# 09_-_Ethernet.net
KiCad netlist of a schematic drawn in Altium Designer
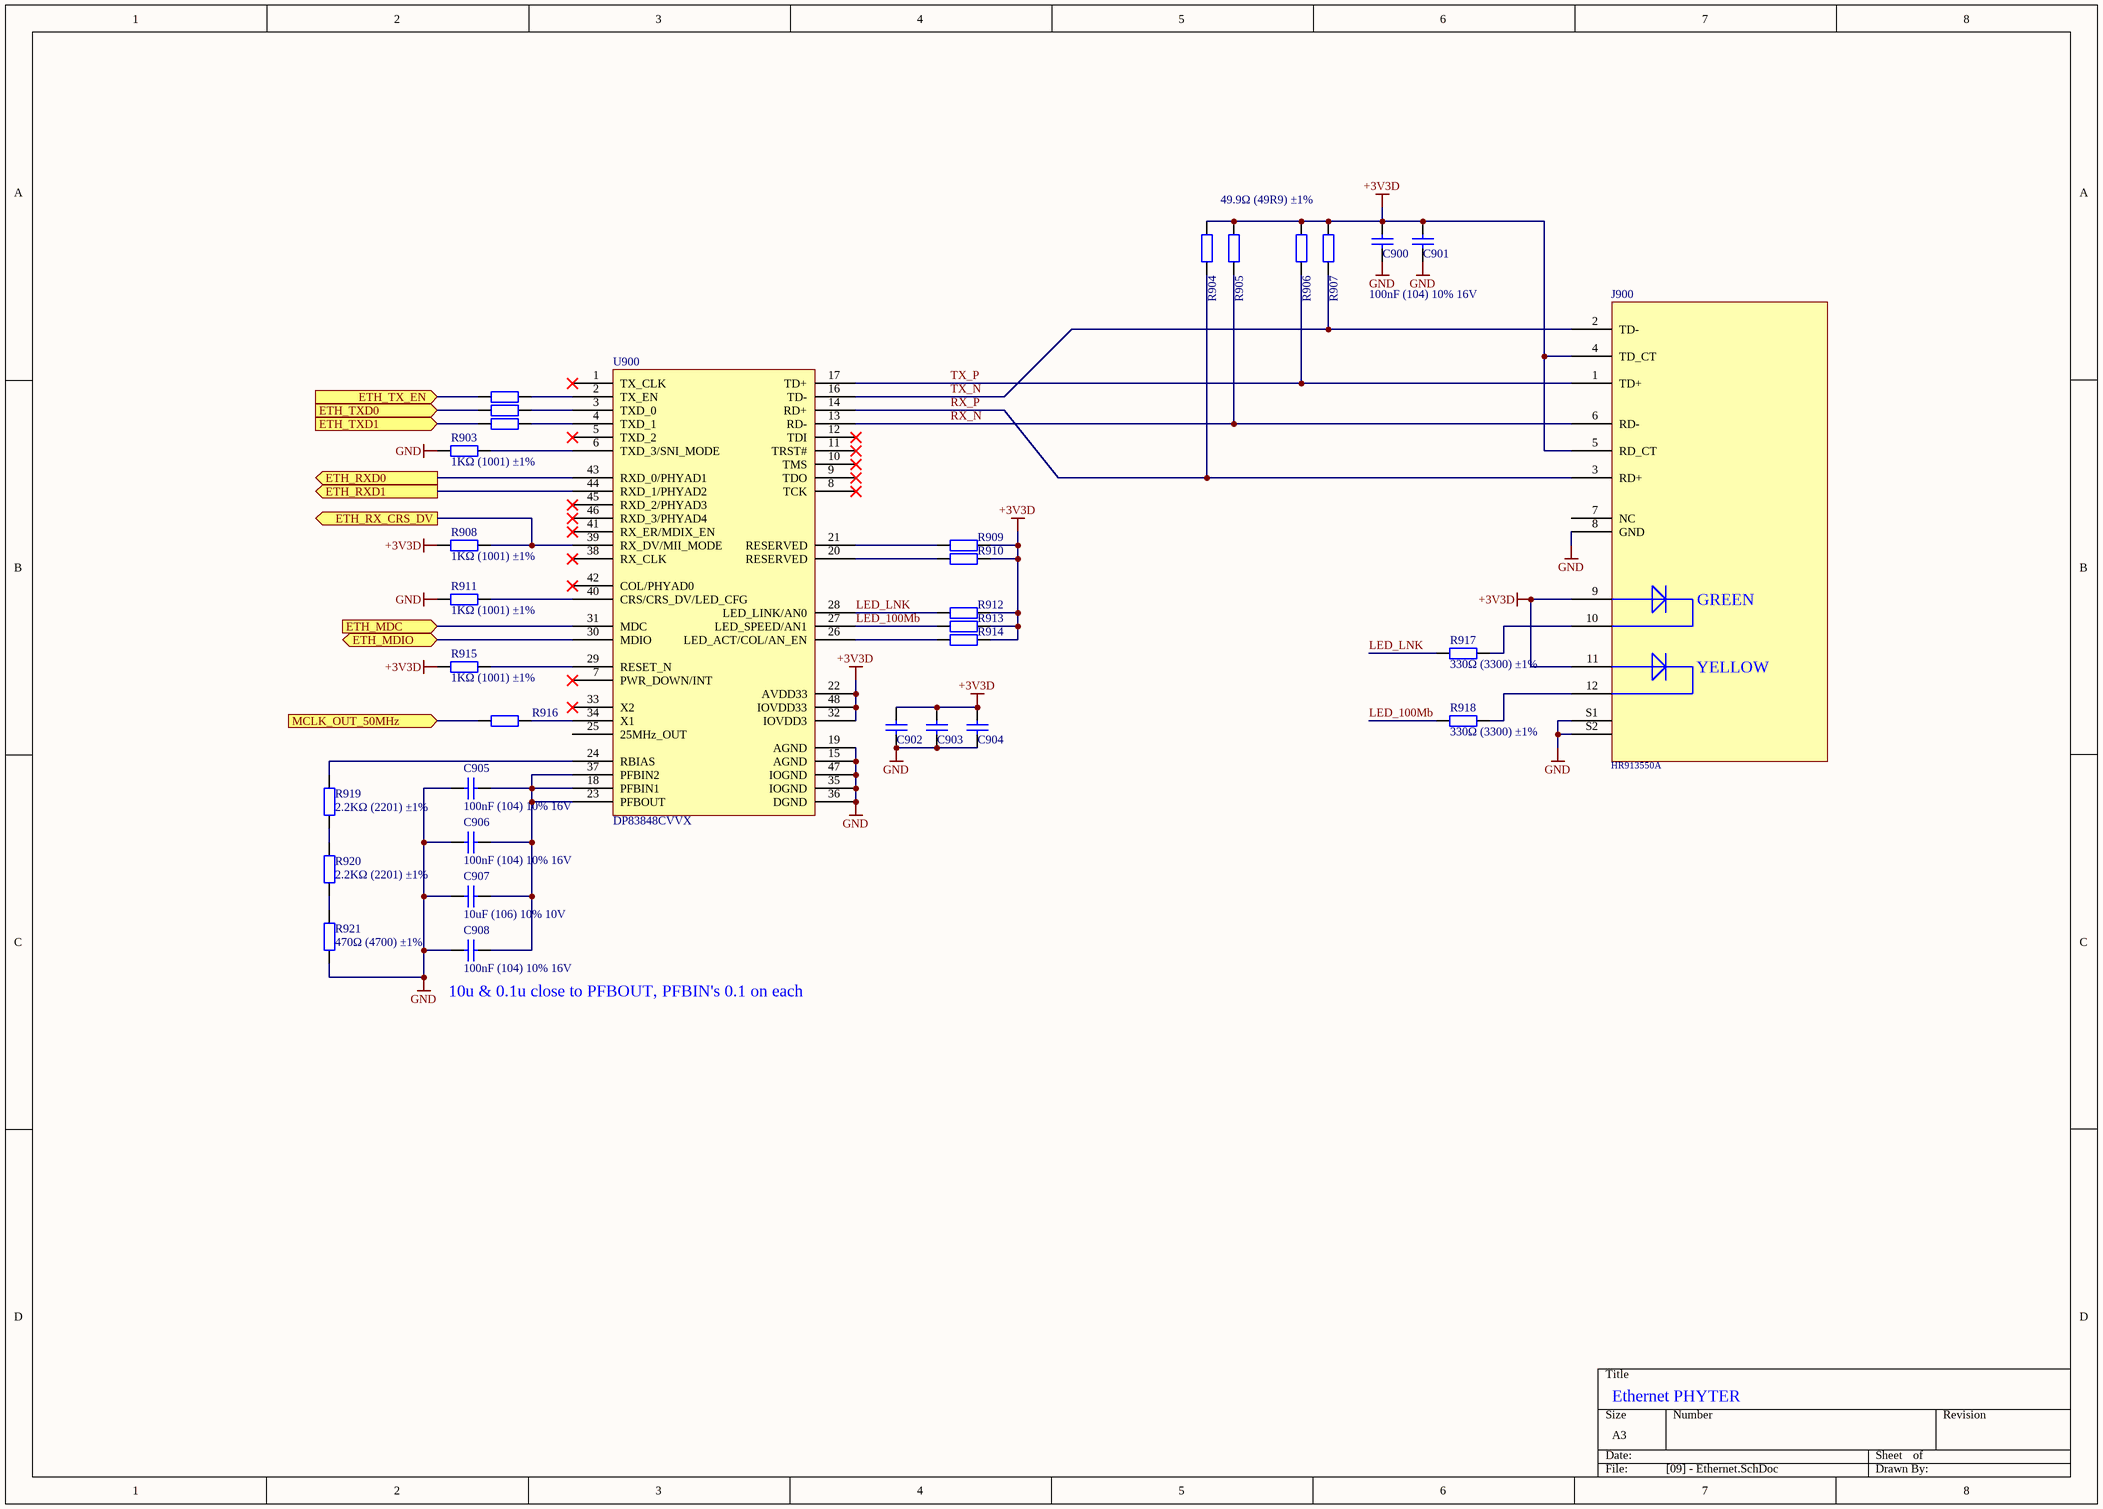
[diagram p0: [09] - Ethernet.SchDoc]

(export (version "E")
  (design (tool "Eeschema 10.0.6"))
  (components
    (comp (ref "C900")
      (value "100nF (104) 10% 16V")
      (footprint "0402_C")
      (description "贴片电容")
      (libsource (lib "Cap") (part "0402 100nF (104) 10% 16V"))
    )
    (comp (ref "C901")
      (value "100nF (104) 10% 16V")
      (footprint "0402_C")
      (description "贴片电容")
      (libsource (lib "Cap") (part "0402 100nF (104) 10% 16V"))
    )
    (comp (ref "C902")
      (value "100nF (104) 10% 16V")
      (footprint "0402_C")
      (description "贴片电容")
      (libsource (lib "Cap") (part "0402 100nF (104) 10% 16V"))
    )
    (comp (ref "C903")
      (value "100nF (104) 10% 16V")
      (footprint "0402_C")
      (description "贴片电容")
      (libsource (lib "Cap") (part "0402 100nF (104) 10% 16V"))
    )
    (comp (ref "C904")
      (value "100nF (104) 10% 16V")
      (footprint "0402_C")
      (description "贴片电容")
      (libsource (lib "Cap") (part "0402 100nF (104) 10% 16V"))
    )
    (comp (ref "C905")
      (value "100nF (104) 10% 16V")
      (footprint "0402_C")
      (description "贴片电容")
      (libsource (lib "Cap") (part "0402 100nF (104) 10% 16V"))
    )
    (comp (ref "C906")
      (value "100nF (104) 10% 16V")
      (footprint "0402_C")
      (description "贴片电容")
      (libsource (lib "Cap") (part "0402 100nF (104) 10% 16V"))
    )
    (comp (ref "C907")
      (value "10uF (106) 10% 10V")
      (footprint "0603_C")
      (description "贴片电容")
      (libsource (lib "Cap") (part "0603 10uF (106) 10% 10V"))
    )
    (comp (ref "C908")
      (value "100nF (104) 10% 16V")
      (footprint "0402_C")
      (description "贴片电容")
      (libsource (lib "Cap") (part "0402 100nF (104) 10% 16V"))
    )
    (comp (ref "J900")
      (value "HR913550A")
      (footprint "RJ45 MagJack")
      (description "RJ45 12 1 Green - Yellow Through Hole Ethernet Connectors/Modular Connectors (RJ45 RJ11) RoHS")
      (libsource (lib "FPGA_PMU_lib") (part "HR913550A"))
    )
    (comp (ref "R900")
      (value "49.9Ω (49R9) ±1%")
      (footprint "0402_R")
      (description "贴片电阻")
      (libsource (lib "RES") (part "0402 49.9Ω (49R9) 1%"))
    )
    (comp (ref "R901")
      (value "49.9Ω (49R9) ±1%")
      (footprint "0402_R")
      (description "贴片电阻")
      (libsource (lib "RES") (part "0402 49.9Ω (49R9) 1%"))
    )
    (comp (ref "R902")
      (value "49.9Ω (49R9) ±1%")
      (footprint "0402_R")
      (description "贴片电阻")
      (libsource (lib "RES") (part "0402 49.9Ω (49R9) 1%"))
    )
    (comp (ref "R903")
      (value "1KΩ (1001) ±1%")
      (footprint "0402_R")
      (description "贴片电阻")
      (libsource (lib "RES") (part "0402 1KΩ (1001) 1%"))
    )
    (comp (ref "R904")
      (value "49.9Ω (49R9) ±1%")
      (footprint "0402_R")
      (description "贴片电阻")
      (libsource (lib "") (part "0402 49.9Ω (49R9) 1%_1"))
    )
    (comp (ref "R905")
      (value "49.9Ω (49R9) ±1%")
      (footprint "0402_R")
      (description "贴片电阻")
      (libsource (lib "") (part "0402 49.9Ω (49R9) 1%_1"))
    )
    (comp (ref "R906")
      (value "49.9Ω (49R9) ±1%")
      (footprint "0402_R")
      (description "贴片电阻")
      (libsource (lib "") (part "0402 49.9Ω (49R9) 1%_1"))
    )
    (comp (ref "R907")
      (value "49.9Ω (49R9) ±1%")
      (footprint "0402_R")
      (description "贴片电阻")
      (libsource (lib "") (part "0402 49.9Ω (49R9) 1%_1"))
    )
    (comp (ref "R908")
      (value "1KΩ (1001) ±1%")
      (footprint "0402_R")
      (description "贴片电阻")
      (libsource (lib "RES") (part "0402 1KΩ (1001) 1%"))
    )
    (comp (ref "R909")
      (value "2.2KΩ (2201) ±1%")
      (footprint "0402_R")
      (description "贴片电阻")
      (libsource (lib "RES") (part "0402 2.2KΩ (2201) 1%"))
    )
    (comp (ref "R910")
      (value "2.2KΩ (2201) ±1%")
      (footprint "0402_R")
      (description "贴片电阻")
      (libsource (lib "RES") (part "0402 2.2KΩ (2201) 1%"))
    )
    (comp (ref "R911")
      (value "1KΩ (1001) ±1%")
      (footprint "0402_R")
      (description "贴片电阻")
      (libsource (lib "RES") (part "0402 1KΩ (1001) 1%"))
    )
    (comp (ref "R912")
      (value "2.2KΩ (2201) ±1%")
      (footprint "0402_R")
      (description "贴片电阻")
      (libsource (lib "RES") (part "0402 2.2KΩ (2201) 1%"))
    )
    (comp (ref "R913")
      (value "2.2KΩ (2201) ±1%")
      (footprint "0402_R")
      (description "贴片电阻")
      (libsource (lib "RES") (part "0402 2.2KΩ (2201) 1%"))
    )
    (comp (ref "R914")
      (value "2.2KΩ (2201) ±1%")
      (footprint "0402_R")
      (description "贴片电阻")
      (libsource (lib "RES") (part "0402 2.2KΩ (2201) 1%"))
    )
    (comp (ref "R915")
      (value "1KΩ (1001) ±1%")
      (footprint "0402_R")
      (description "贴片电阻")
      (libsource (lib "RES") (part "0402 1KΩ (1001) 1%"))
    )
    (comp (ref "R916")
      (value "49.9Ω (49R9) ±1%")
      (footprint "0402_R")
      (description "贴片电阻")
      (libsource (lib "RES") (part "0402 49.9Ω (49R9) 1%"))
    )
    (comp (ref "R917")
      (value "330Ω (3300) ±1%")
      (footprint "0603_R")
      (description "贴片电阻")
      (libsource (lib "RES") (part "0603 330Ω (3300) 1%"))
    )
    (comp (ref "R918")
      (value "330Ω (3300) ±1%")
      (footprint "0603_R")
      (description "贴片电阻")
      (libsource (lib "RES") (part "0603 330Ω (3300) 1%"))
    )
    (comp (ref "R919")
      (value "2.2KΩ (2201) ±1%")
      (footprint "0402_R")
      (description "贴片电阻")
      (libsource (lib "") (part "0402 2.2KΩ (2201) 1%_1"))
    )
    (comp (ref "R920")
      (value "2.2KΩ (2201) ±1%")
      (footprint "0402_R")
      (description "贴片电阻")
      (libsource (lib "") (part "0402 2.2KΩ (2201) 1%_1"))
    )
    (comp (ref "R921")
      (value "470Ω (4700) ±1%")
      (footprint "0402_R")
      (description "贴片电阻")
      (libsource (lib "RES") (part "0402 470Ω (4700) 1%"))
    )
    (comp (ref "U900")
      (value "DP83848CVVX")
      (footprint "LQFP-48_7x7x05P")
      (description "接口芯片")
      (libsource (lib "IC") (part "DP83848CVVX_[C16688]"))
    )
  )
  (nets
    (net (code "1") (name "+3V3D") (class "Default")
      (node (ref "C900") (pin "2") (pinfunction "2_2") (pintype "passive"))
      (node (ref "C901") (pin "2") (pinfunction "2_2") (pintype "passive"))
      (node (ref "C902") (pin "2") (pinfunction "2_2") (pintype "passive"))
      (node (ref "C903") (pin "2") (pinfunction "2_2") (pintype "passive"))
      (node (ref "C904") (pin "2") (pinfunction "2_2") (pintype "passive"))
      (node (ref "J900") (pin "11") (pinfunction "11_11") (pintype "passive"))
      (node (ref "J900") (pin "4") (pinfunction "TD_CT_4") (pintype "passive"))
      (node (ref "J900") (pin "5") (pinfunction "RD_CT_5") (pintype "passive"))
      (node (ref "J900") (pin "9") (pinfunction "9_9") (pintype "passive"))
      (node (ref "R904") (pin "2") (pinfunction "2_2") (pintype "passive"))
      (node (ref "R905") (pin "2") (pinfunction "2_2") (pintype "passive"))
      (node (ref "R906") (pin "2") (pinfunction "2_2") (pintype "passive"))
      (node (ref "R907") (pin "2") (pinfunction "2_2") (pintype "passive"))
      (node (ref "R908") (pin "1") (pinfunction "1_1") (pintype "passive"))
      (node (ref "R909") (pin "2") (pinfunction "2_2") (pintype "passive"))
      (node (ref "R910") (pin "2") (pinfunction "2_2") (pintype "passive"))
      (node (ref "R912") (pin "2") (pinfunction "2_2") (pintype "passive"))
      (node (ref "R913") (pin "2") (pinfunction "2_2") (pintype "passive"))
      (node (ref "R914") (pin "2") (pinfunction "2_2") (pintype "passive"))
      (node (ref "R915") (pin "1") (pinfunction "1_1") (pintype "passive"))
      (node (ref "U900") (pin "22") (pinfunction "AVDD33_22") (pintype "passive"))
      (node (ref "U900") (pin "32") (pinfunction "IOVDD3_32") (pintype "passive"))
      (node (ref "U900") (pin "48") (pinfunction "IOVDD33_48") (pintype "passive"))
    )
    (net (code "2") (name "/ETH_MDC") (class "Default")
      (node (ref "U900") (pin "31") (pinfunction "MDC_31") (pintype "passive"))
    )
    (net (code "3") (name "/ETH_MDIO") (class "Default")
      (node (ref "U900") (pin "30") (pinfunction "MDIO_30") (pintype "passive"))
    )
    (net (code "4") (name "/ETH_RXD0") (class "Default")
      (node (ref "U900") (pin "43") (pinfunction "RXD_0/PHYAD1_43") (pintype "passive"))
    )
    (net (code "5") (name "/ETH_RXD1") (class "Default")
      (node (ref "U900") (pin "44") (pinfunction "RXD_1/PHYAD2_44") (pintype "passive"))
    )
    (net (code "6") (name "/ETH_RX_CRS_DV") (class "Default")
      (node (ref "R908") (pin "2") (pinfunction "2_2") (pintype "passive"))
      (node (ref "U900") (pin "39") (pinfunction "RX_DV/MII_MODE_39") (pintype "passive"))
    )
    (net (code "7") (name "/ETH_TXD0") (class "Default")
      (node (ref "R901") (pin "1") (pinfunction "1_1") (pintype "passive"))
    )
    (net (code "8") (name "/ETH_TXD1") (class "Default")
      (node (ref "R902") (pin "1") (pinfunction "1_1") (pintype "passive"))
    )
    (net (code "9") (name "/ETH_TX_EN") (class "Default")
      (node (ref "R900") (pin "1") (pinfunction "1_1") (pintype "passive"))
    )
    (net (code "10") (name "/LED_100Mb") (class "Default")
      (node (ref "R913") (pin "1") (pinfunction "1_1") (pintype "passive"))
      (node (ref "R918") (pin "1") (pinfunction "1_1") (pintype "passive"))
      (node (ref "U900") (pin "27") (pinfunction "LED_SPEED/AN1_27") (pintype "passive"))
    )
    (net (code "11") (name "/LED_LNK") (class "Default")
      (node (ref "R912") (pin "1") (pinfunction "1_1") (pintype "passive"))
      (node (ref "R917") (pin "1") (pinfunction "1_1") (pintype "passive"))
      (node (ref "U900") (pin "28") (pinfunction "LED_LINK/AN0_28") (pintype "passive"))
    )
    (net (code "12") (name "/MCLK_OUT_50MHz") (class "Default")
      (node (ref "R916") (pin "1") (pinfunction "1_1") (pintype "passive"))
    )
    (net (code "13") (name "/RX_N") (class "Default")
      (node (ref "J900") (pin "6") (pinfunction "RD-_6") (pintype "passive"))
      (node (ref "R905") (pin "1") (pinfunction "1_1") (pintype "passive"))
      (node (ref "U900") (pin "13") (pinfunction "RD-_13") (pintype "passive"))
    )
    (net (code "14") (name "/RX_P") (class "Default")
      (node (ref "J900") (pin "3") (pinfunction "RD+_3") (pintype "passive"))
      (node (ref "R904") (pin "1") (pinfunction "1_1") (pintype "passive"))
      (node (ref "U900") (pin "14") (pinfunction "RD+_14") (pintype "passive"))
    )
    (net (code "15") (name "/TX_N") (class "Default")
      (node (ref "J900") (pin "2") (pinfunction "TD-_2") (pintype "passive"))
      (node (ref "R907") (pin "1") (pinfunction "1_1") (pintype "passive"))
      (node (ref "U900") (pin "16") (pinfunction "TD-_16") (pintype "passive"))
    )
    (net (code "16") (name "/TX_P") (class "Default")
      (node (ref "J900") (pin "1") (pinfunction "TD+_1") (pintype "passive"))
      (node (ref "R906") (pin "1") (pinfunction "1_1") (pintype "passive"))
      (node (ref "U900") (pin "17") (pinfunction "TD+_17") (pintype "passive"))
    )
    (net (code "17") (name "GND") (class "Default")
      (node (ref "C900") (pin "1") (pinfunction "1_1") (pintype "passive"))
      (node (ref "C901") (pin "1") (pinfunction "1_1") (pintype "passive"))
      (node (ref "C902") (pin "1") (pinfunction "1_1") (pintype "passive"))
      (node (ref "C903") (pin "1") (pinfunction "1_1") (pintype "passive"))
      (node (ref "C904") (pin "1") (pinfunction "1_1") (pintype "passive"))
      (node (ref "C905") (pin "1") (pinfunction "1_1") (pintype "passive"))
      (node (ref "C906") (pin "1") (pinfunction "1_1") (pintype "passive"))
      (node (ref "C907") (pin "1") (pinfunction "1_1") (pintype "passive"))
      (node (ref "C908") (pin "1") (pinfunction "1_1") (pintype "passive"))
      (node (ref "J900") (pin "8") (pinfunction "GND_8") (pintype "passive"))
      (node (ref "J900") (pin "S1") (pinfunction "S1_S1") (pintype "passive"))
      (node (ref "J900") (pin "S2") (pinfunction "S2_S2") (pintype "passive"))
      (node (ref "R903") (pin "1") (pinfunction "1_1") (pintype "passive"))
      (node (ref "R911") (pin "1") (pinfunction "1_1") (pintype "passive"))
      (node (ref "R921") (pin "1") (pinfunction "1_1") (pintype "passive"))
      (node (ref "U900") (pin "15") (pinfunction "AGND_15") (pintype "passive"))
      (node (ref "U900") (pin "19") (pinfunction "AGND_19") (pintype "passive"))
      (node (ref "U900") (pin "35") (pinfunction "IOGND_35") (pintype "passive"))
      (node (ref "U900") (pin "36") (pinfunction "DGND_36") (pintype "passive"))
      (node (ref "U900") (pin "47") (pinfunction "IOGND_47") (pintype "passive"))
    )
    (net (code "18") (name "Net-(J900-Pad10)") (class "Default")
      (node (ref "J900") (pin "10") (pinfunction "10_10") (pintype "passive"))
      (node (ref "R917") (pin "2") (pinfunction "2_2") (pintype "passive"))
    )
    (net (code "19") (name "Net-(J900-Pad12)") (class "Default")
      (node (ref "J900") (pin "12") (pinfunction "12_12") (pintype "passive"))
      (node (ref "R918") (pin "2") (pinfunction "2_2") (pintype "passive"))
    )
    (net (code "20") (name "Net-(R909-Pad1)") (class "Default")
      (node (ref "R909") (pin "1") (pinfunction "1_1") (pintype "passive"))
      (node (ref "U900") (pin "21") (pinfunction "RESERVED_21") (pintype "passive"))
    )
    (net (code "21") (name "Net-(R910-Pad1)") (class "Default")
      (node (ref "R910") (pin "1") (pinfunction "1_1") (pintype "passive"))
      (node (ref "U900") (pin "20") (pinfunction "RESERVED_20") (pintype "passive"))
    )
    (net (code "22") (name "Net-(R919-Pad1)") (class "Default")
      (node (ref "R919") (pin "1") (pinfunction "1_1") (pintype "passive"))
      (node (ref "R920") (pin "2") (pinfunction "2_2") (pintype "passive"))
    )
    (net (code "23") (name "Net-(R920-Pad1)") (class "Default")
      (node (ref "R920") (pin "1") (pinfunction "1_1") (pintype "passive"))
      (node (ref "R921") (pin "2") (pinfunction "2_2") (pintype "passive"))
    )
    (net (code "24") (name "Net-(U900-CRS{slash}CRS_DV{slash}LED_CFG)") (class "Default")
      (node (ref "R911") (pin "2") (pinfunction "2_2") (pintype "passive"))
      (node (ref "U900") (pin "40") (pinfunction "CRS/CRS_DV/LED_CFG_40") (pintype "passive"))
    )
    (net (code "25") (name "Net-(U900-LED_ACT{slash}COL{slash}AN_EN)") (class "Default")
      (node (ref "R914") (pin "1") (pinfunction "1_1") (pintype "passive"))
      (node (ref "U900") (pin "26") (pinfunction "LED_ACT/COL/AN_EN_26") (pintype "passive"))
    )
    (net (code "26") (name "Net-(U900-PFBIN1)") (class "Default")
      (node (ref "C905") (pin "2") (pinfunction "2_2") (pintype "passive"))
      (node (ref "C906") (pin "2") (pinfunction "2_2") (pintype "passive"))
      (node (ref "C907") (pin "2") (pinfunction "2_2") (pintype "passive"))
      (node (ref "C908") (pin "2") (pinfunction "2_2") (pintype "passive"))
      (node (ref "U900") (pin "18") (pinfunction "PFBIN1_18") (pintype "passive"))
      (node (ref "U900") (pin "23") (pinfunction "PFBOUT_23") (pintype "passive"))
      (node (ref "U900") (pin "37") (pinfunction "PFBIN2_37") (pintype "passive"))
    )
    (net (code "27") (name "Net-(U900-RBIAS)") (class "Default")
      (node (ref "R919") (pin "2") (pinfunction "2_2") (pintype "passive"))
      (node (ref "U900") (pin "24") (pinfunction "RBIAS_24") (pintype "passive"))
    )
    (net (code "28") (name "Net-(U900-RESET_N)") (class "Default")
      (node (ref "R915") (pin "2") (pinfunction "2_2") (pintype "passive"))
      (node (ref "U900") (pin "29") (pinfunction "RESET_N_29") (pintype "passive"))
    )
    (net (code "29") (name "Net-(U900-TXD_0)") (class "Default")
      (node (ref "R901") (pin "2") (pinfunction "2_2") (pintype "passive"))
      (node (ref "U900") (pin "3") (pinfunction "TXD_0_3") (pintype "passive"))
    )
    (net (code "30") (name "Net-(U900-TXD_1)") (class "Default")
      (node (ref "R902") (pin "2") (pinfunction "2_2") (pintype "passive"))
      (node (ref "U900") (pin "4") (pinfunction "TXD_1_4") (pintype "passive"))
    )
    (net (code "31") (name "Net-(U900-TXD_3{slash}SNI_MODE)") (class "Default")
      (node (ref "R903") (pin "2") (pinfunction "2_2") (pintype "passive"))
      (node (ref "U900") (pin "6") (pinfunction "TXD_3/SNI_MODE_6") (pintype "passive"))
    )
    (net (code "32") (name "Net-(U900-TX_EN)") (class "Default")
      (node (ref "R900") (pin "2") (pinfunction "2_2") (pintype "passive"))
      (node (ref "U900") (pin "2") (pinfunction "TX_EN_2") (pintype "passive"))
    )
    (net (code "33") (name "Net-(U900-X1)") (class "Default")
      (node (ref "R916") (pin "2") (pinfunction "2_2") (pintype "passive"))
      (node (ref "U900") (pin "34") (pinfunction "X1_34") (pintype "passive"))
    )
    (net (code "34") (name "unconnected-(J900-NC-Pad7)") (class "Default")
      (node (ref "J900") (pin "7") (pinfunction "NC_7") (pintype "passive"))
    )
    (net (code "35") (name "unconnected-(U900-25MHz_OUT-Pad25)") (class "Default")
      (node (ref "U900") (pin "25") (pinfunction "25MHz_OUT_25") (pintype "passive"))
    )
    (net (code "36") (name "unconnected-(U900-COL{slash}PHYAD0-Pad42)") (class "Default")
      (node (ref "U900") (pin "42") (pinfunction "COL/PHYAD0_42") (pintype "passive+no_connect"))
    )
    (net (code "37") (name "unconnected-(U900-PWR_DOWN{slash}INT-Pad7)") (class "Default")
      (node (ref "U900") (pin "7") (pinfunction "PWR_DOWN/INT_7") (pintype "passive+no_connect"))
    )
    (net (code "38") (name "unconnected-(U900-RXD_2{slash}PHYAD3-Pad45)") (class "Default")
      (node (ref "U900") (pin "45") (pinfunction "RXD_2/PHYAD3_45") (pintype "passive+no_connect"))
    )
    (net (code "39") (name "unconnected-(U900-RXD_3{slash}PHYAD4-Pad46)") (class "Default")
      (node (ref "U900") (pin "46") (pinfunction "RXD_3/PHYAD4_46") (pintype "passive+no_connect"))
    )
    (net (code "40") (name "unconnected-(U900-RX_CLK-Pad38)") (class "Default")
      (node (ref "U900") (pin "38") (pinfunction "RX_CLK_38") (pintype "passive+no_connect"))
    )
    (net (code "41") (name "unconnected-(U900-RX_ER{slash}MDIX_EN-Pad41)") (class "Default")
      (node (ref "U900") (pin "41") (pinfunction "RX_ER/MDIX_EN_41") (pintype "passive+no_connect"))
    )
    (net (code "42") (name "unconnected-(U900-TCK-Pad8)") (class "Default")
      (node (ref "U900") (pin "8") (pinfunction "TCK_8") (pintype "passive+no_connect"))
    )
    (net (code "43") (name "unconnected-(U900-TDI-Pad12)") (class "Default")
      (node (ref "U900") (pin "12") (pinfunction "TDI_12") (pintype "passive+no_connect"))
    )
    (net (code "44") (name "unconnected-(U900-TDO-Pad9)") (class "Default")
      (node (ref "U900") (pin "9") (pinfunction "TDO_9") (pintype "passive+no_connect"))
    )
    (net (code "45") (name "unconnected-(U900-TMS-Pad10)") (class "Default")
      (node (ref "U900") (pin "10") (pinfunction "TMS_10") (pintype "passive+no_connect"))
    )
    (net (code "46") (name "unconnected-(U900-TRST#-Pad11)") (class "Default")
      (node (ref "U900") (pin "11") (pinfunction "TRST#_11") (pintype "passive+no_connect"))
    )
    (net (code "47") (name "unconnected-(U900-TXD_2-Pad5)") (class "Default")
      (node (ref "U900") (pin "5") (pinfunction "TXD_2_5") (pintype "passive+no_connect"))
    )
    (net (code "48") (name "unconnected-(U900-TX_CLK-Pad1)") (class "Default")
      (node (ref "U900") (pin "1") (pinfunction "TX_CLK_1") (pintype "passive+no_connect"))
    )
    (net (code "49") (name "unconnected-(U900-X2-Pad33)") (class "Default")
      (node (ref "U900") (pin "33") (pinfunction "X2_33") (pintype "passive+no_connect"))
    )
  )
)
